# SCH_MotorDriver_2025-03-28.net
KiCad netlist of a schematic drawn in EasyEDA
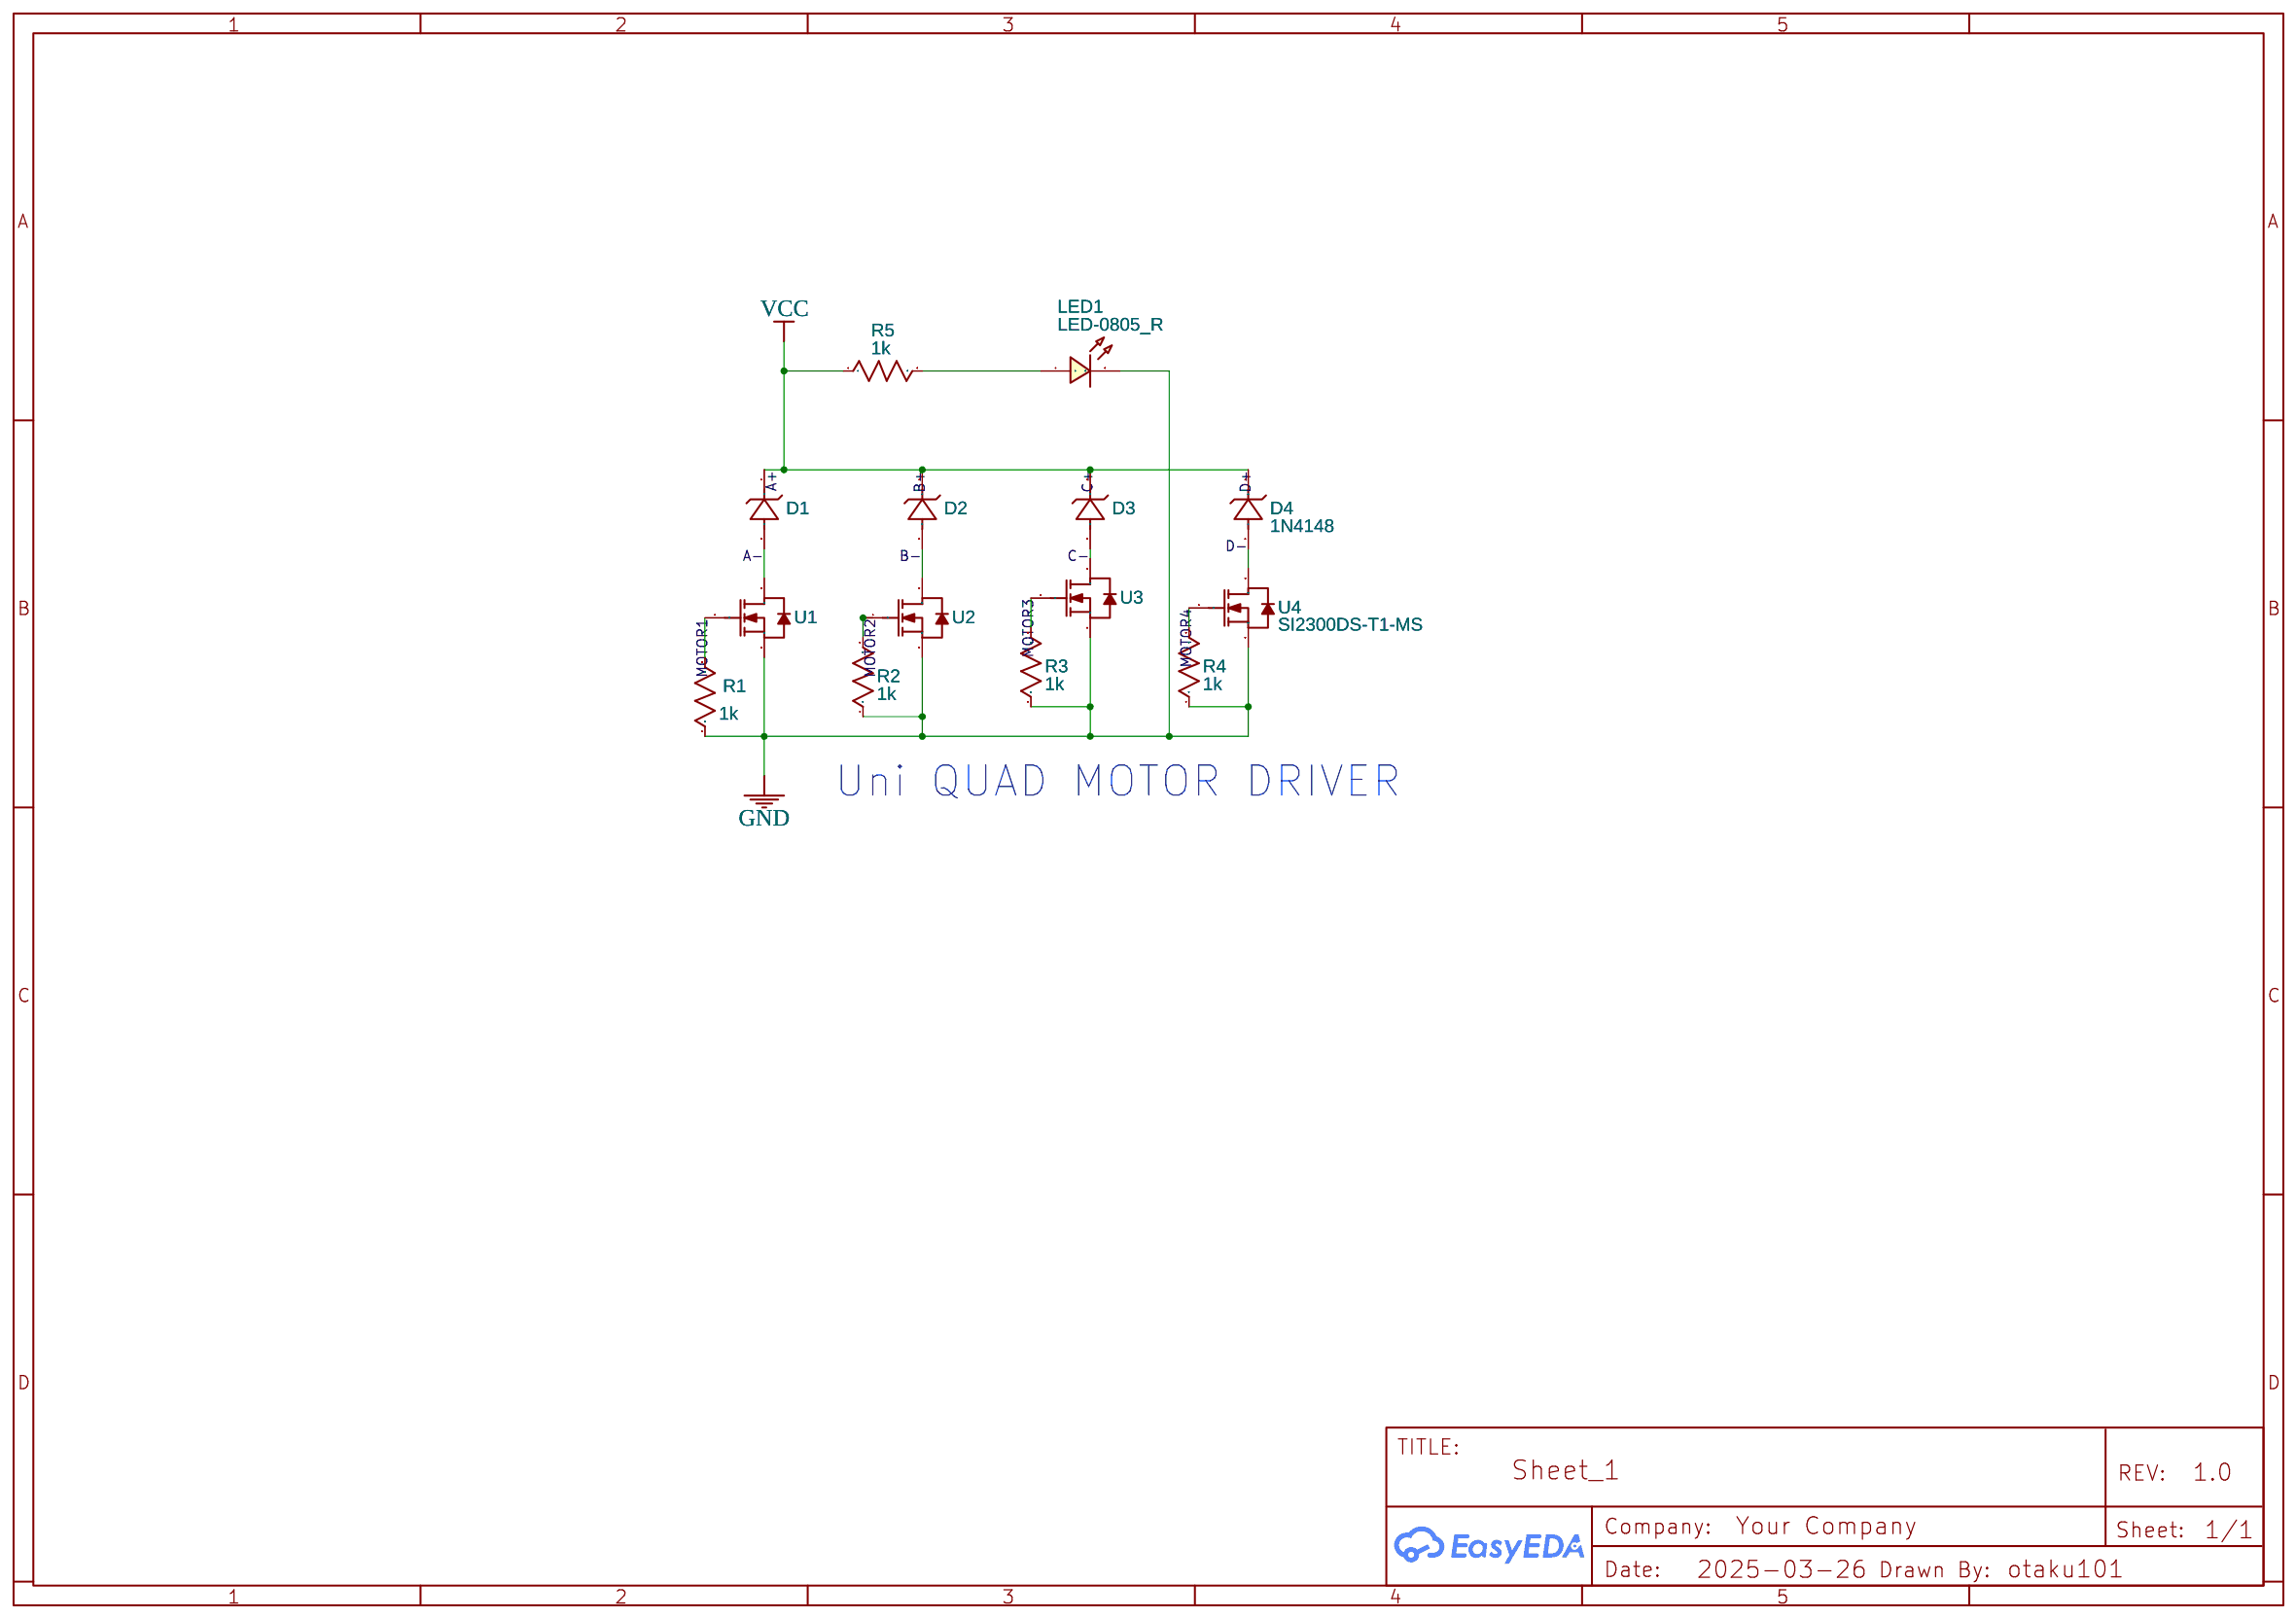
[diagram p0: schematic sheet]

(export (version "E")
  (design (tool "Eeschema 10.0.6"))
  (components
    (comp (ref "D1")
      (value "WFR1N4148WT")
      (fields (field (name "Manufacturer") "Wayon(上海维安)"))
      (libsource (lib "") (part "WFR1N4148WT"))
    )
    (comp (ref "D2")
      (value "WFR1N4148WT")
      (fields (field (name "Manufacturer") "Wayon(上海维安)"))
      (libsource (lib "") (part "WFR1N4148WT"))
    )
    (comp (ref "D3")
      (value "WFR1N4148WT")
      (fields (field (name "Manufacturer") "Wayon(上海维安)"))
      (libsource (lib "") (part "WFR1N4148WT"))
    )
    (comp (ref "D4")
      (value "1N4148")
      (fields (field (name "Manufacturer Part") "WFR1N4148WT") (field (name "Manufacturer") "Wayon(上海维安)"))
      (libsource (lib "") (part "WFR1N4148WT"))
    )
    (comp (ref "LED1")
      (value "LED-0805_R")
      (fields
        (field (name "Manufacturer Part") "17-21SURC/S530-A3/TR8")
        (field (name "Manufacturer") "EVERLIGHT(台湾亿光)")
      )
      (libsource (lib "") (part "LED-0805_R"))
    )
    (comp (ref "R1") (value "1k") (libsource (lib "") (part "R_0805_US")))
    (comp (ref "R2") (value "1k") (libsource (lib "") (part "R_0805_US")))
    (comp (ref "R3") (value "1k") (libsource (lib "") (part "R_0805_US")))
    (comp (ref "R4") (value "1k") (libsource (lib "") (part "R_0805_US")))
    (comp (ref "R5") (value "1k") (libsource (lib "") (part "R_0805_US_1")))
    (comp (ref "U1")
      (value "SI2300DS-T1-MS")
      (fields (field (name "Manufacturer") "MSKSEMI(美森科)"))
      (libsource (lib "") (part "SI2300DS-T1-MS"))
    )
    (comp (ref "U2")
      (value "SI2300DS-T1-MS")
      (fields (field (name "Manufacturer") "MSKSEMI(美森科)"))
      (libsource (lib "") (part "SI2300DS-T1-MS"))
    )
    (comp (ref "U3")
      (value "SI2300DS-T1-MS")
      (fields (field (name "Manufacturer") "MSKSEMI(美森科)"))
      (libsource (lib "") (part "SI2300DS-T1-MS"))
    )
    (comp (ref "U4")
      (value "SI2300DS-T1-MS")
      (fields (field (name "Manufacturer") "MSKSEMI(美森科)"))
      (libsource (lib "") (part "SI2300DS-T1-MS"))
    )
  )
  (nets
    (net (code "1") (name "/A-") (class "Default")
      (node (ref "D1") (pin "2") (pinfunction "A_2") (pintype "unspecified"))
      (node (ref "U1") (pin "3") (pinfunction "D_3") (pintype "unspecified"))
    )
    (net (code "2") (name "/B-") (class "Default")
      (node (ref "D2") (pin "2") (pinfunction "A_2") (pintype "unspecified"))
      (node (ref "U2") (pin "3") (pinfunction "D_3") (pintype "unspecified"))
    )
    (net (code "3") (name "/C-") (class "Default")
      (node (ref "D3") (pin "2") (pinfunction "A_2") (pintype "unspecified"))
      (node (ref "U3") (pin "3") (pinfunction "D_3") (pintype "unspecified"))
    )
    (net (code "4") (name "/D-") (class "Default")
      (node (ref "D4") (pin "2") (pinfunction "A_2") (pintype "unspecified"))
      (node (ref "U4") (pin "3") (pinfunction "D_3") (pintype "unspecified"))
    )
    (net (code "5") (name "/MOTOR1") (class "Default")
      (node (ref "R1") (pin "2") (pinfunction "2_2") (pintype "unspecified"))
      (node (ref "U1") (pin "1") (pinfunction "G_1") (pintype "unspecified"))
    )
    (net (code "6") (name "/MOTOR2") (class "Default")
      (node (ref "R2") (pin "2") (pinfunction "2_2") (pintype "unspecified"))
      (node (ref "U2") (pin "1") (pinfunction "G_1") (pintype "unspecified"))
    )
    (net (code "7") (name "/MOTOR3") (class "Default")
      (node (ref "R3") (pin "2") (pinfunction "2_2") (pintype "unspecified"))
      (node (ref "U3") (pin "1") (pinfunction "G_1") (pintype "unspecified"))
    )
    (net (code "8") (name "/MOTOR4") (class "Default")
      (node (ref "R4") (pin "2") (pinfunction "2_2") (pintype "unspecified"))
      (node (ref "U4") (pin "1") (pinfunction "G_1") (pintype "unspecified"))
    )
    (net (code "9") (name "GND") (class "Default")
      (node (ref "LED1") (pin "2") (pinfunction "2_2") (pintype "unspecified"))
      (node (ref "R1") (pin "1") (pinfunction "1_1") (pintype "unspecified"))
      (node (ref "R2") (pin "1") (pinfunction "1_1") (pintype "unspecified"))
      (node (ref "R3") (pin "1") (pinfunction "1_1") (pintype "unspecified"))
      (node (ref "R4") (pin "1") (pinfunction "1_1") (pintype "unspecified"))
      (node (ref "U1") (pin "2") (pinfunction "S_2") (pintype "unspecified"))
      (node (ref "U2") (pin "2") (pinfunction "S_2") (pintype "unspecified"))
      (node (ref "U3") (pin "2") (pinfunction "S_2") (pintype "unspecified"))
      (node (ref "U4") (pin "2") (pinfunction "S_2") (pintype "unspecified"))
    )
    (net (code "10") (name "Net-(LED1-Pad1)") (class "Default")
      (node (ref "LED1") (pin "1") (pinfunction "1_1") (pintype "unspecified"))
      (node (ref "R5") (pin "2") (pinfunction "2_2") (pintype "unspecified"))
    )
    (net (code "11") (name "VCC") (class "Default")
      (node (ref "D1") (pin "1") (pinfunction "C_1") (pintype "unspecified"))
      (node (ref "D2") (pin "1") (pinfunction "C_1") (pintype "unspecified"))
      (node (ref "D3") (pin "1") (pinfunction "C_1") (pintype "unspecified"))
      (node (ref "D4") (pin "1") (pinfunction "C_1") (pintype "unspecified"))
      (node (ref "R5") (pin "1") (pinfunction "1_1") (pintype "unspecified"))
    )
  )
)
